# LuxLogger_V2_mcu_pwr.net
KiCad netlist of a schematic drawn in Altium Designer
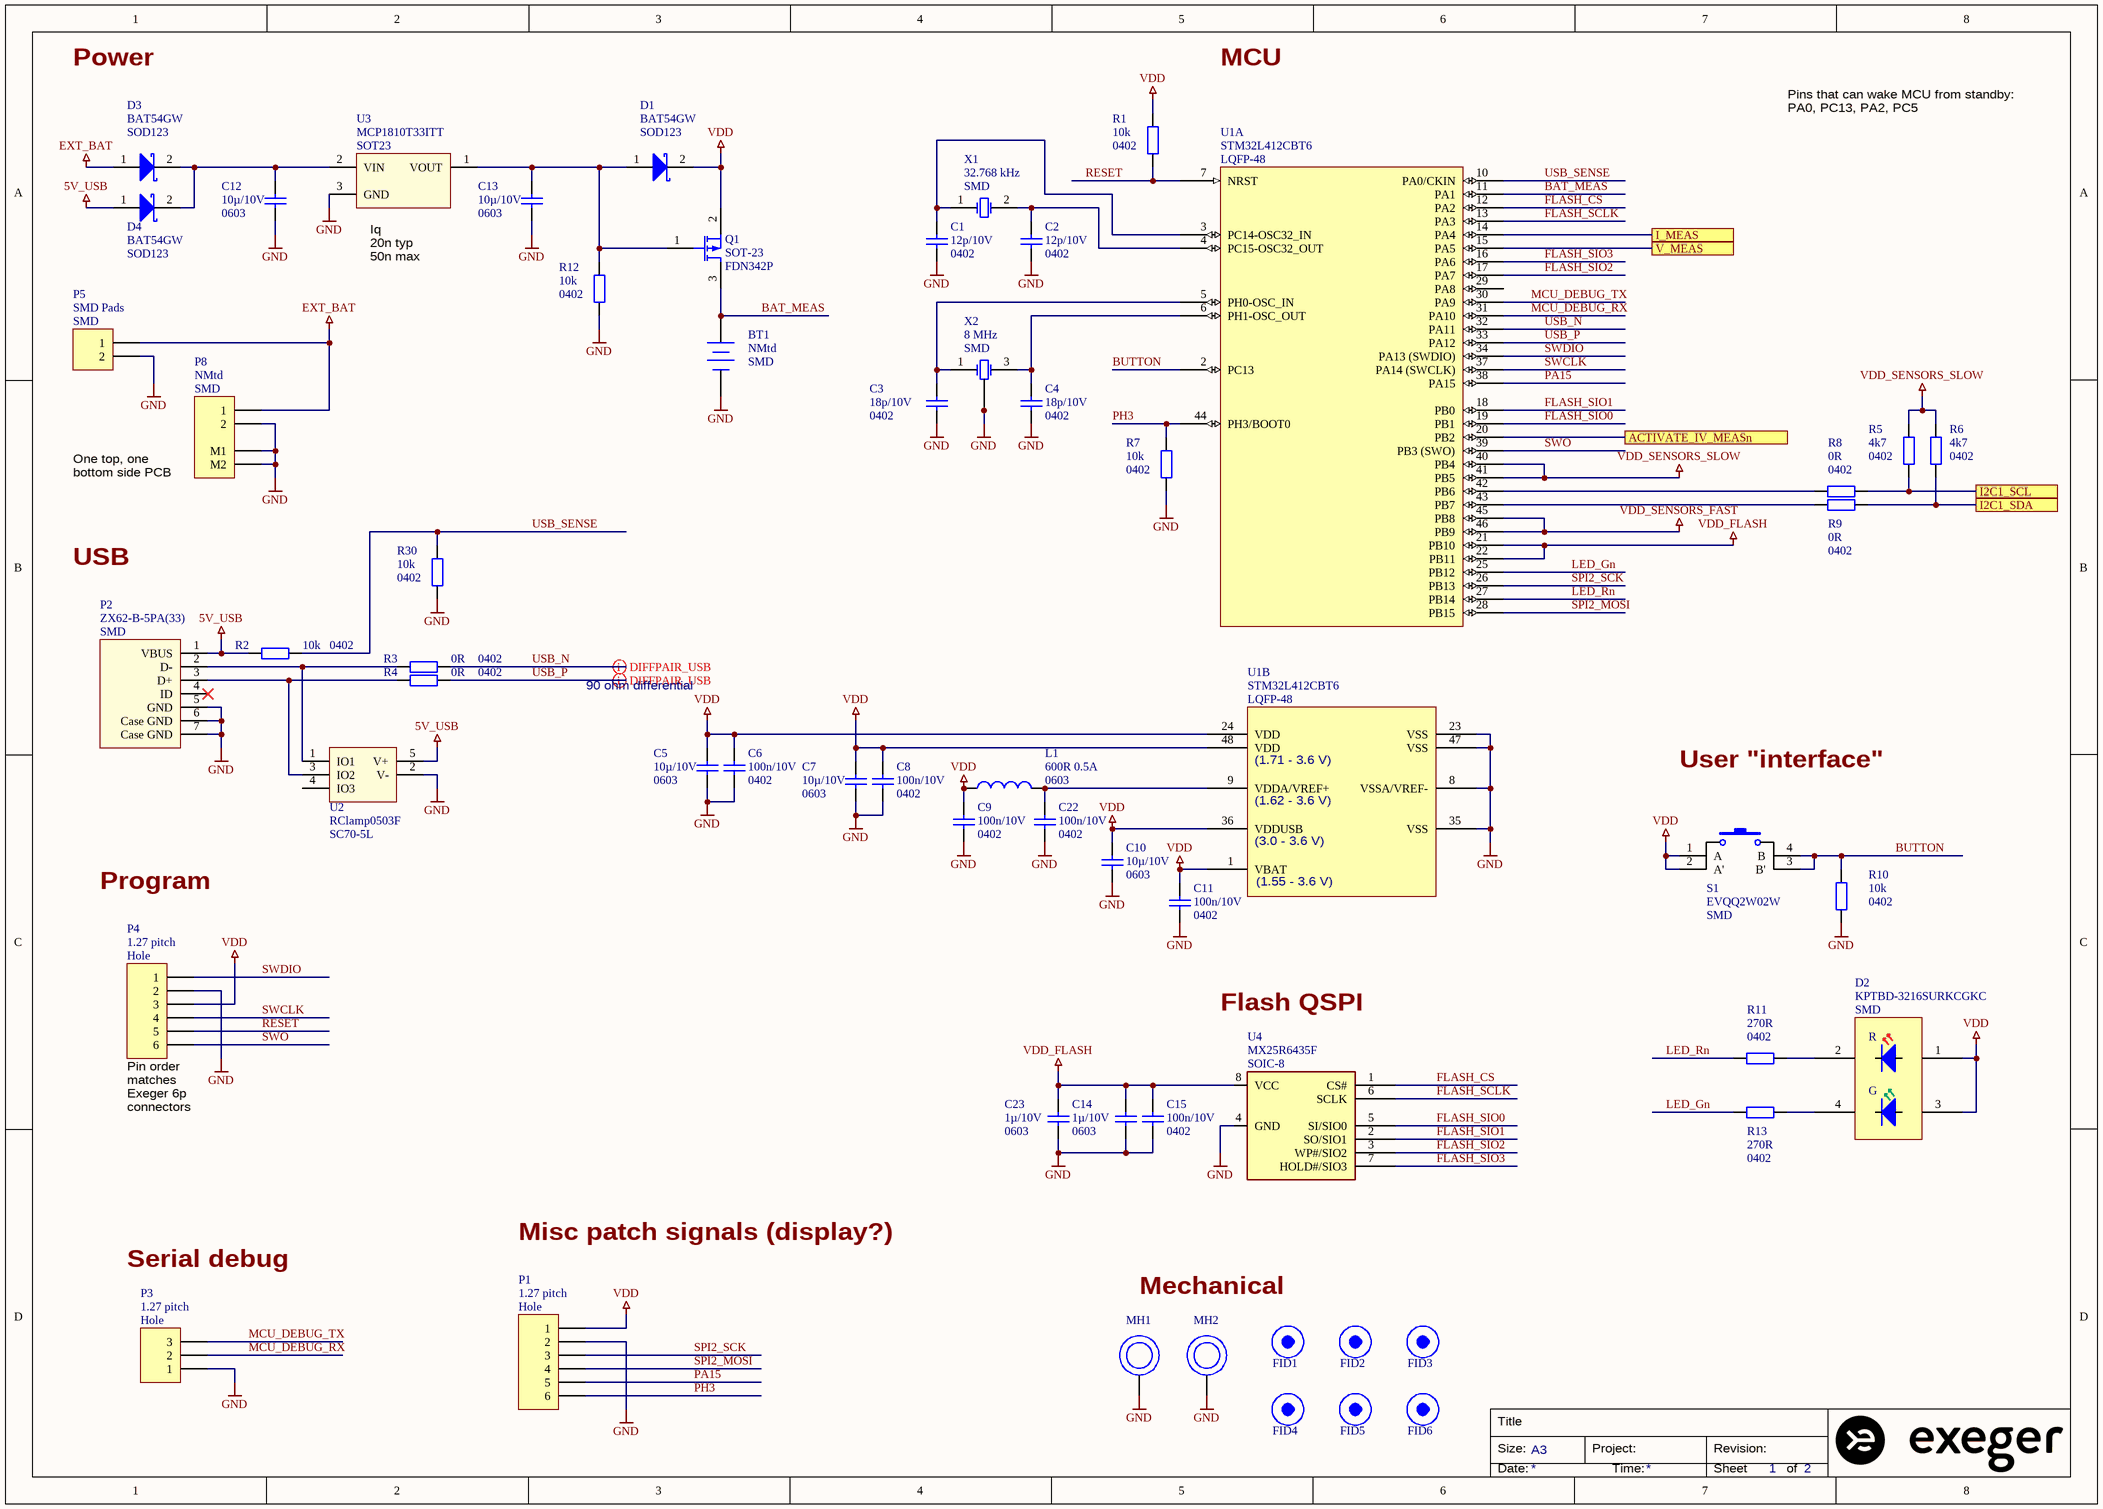
[diagram p0: LuxLogger_V2_mcu_pwr.SchDoc]

(export (version "E")
  (design (tool "Eeschema 10.0.6"))
  (components
    (comp (ref "BT1")
      (value "Alternative BU2032SM-JJ-GTR")
      (footprint "BU2032SM-HD-G")
      (description "CR2032 holder")
      (fields
        (field (name "SPECIFICATION") "NMtd")
        (field (name "PACKAGE") "SMD")
        (field (name "MANUFACTURER") "MPD")
      )
      (libsource (lib "Miscellaneous Devices") (part "Battery"))
    )
    (comp (ref "C1")
      (value "~")
      (footprint "CAP0402")
      (description "Capacitor")
      (fields (field (name "SPECIFICATION") "12p/10V") (field (name "PACKAGE") "0402"))
      (libsource (lib "Miscellaneous Devices") (part "Cap"))
    )
    (comp (ref "C2")
      (value "~")
      (footprint "CAP0402")
      (description "Capacitor")
      (fields (field (name "SPECIFICATION") "12p/10V") (field (name "PACKAGE") "0402"))
      (libsource (lib "Miscellaneous Devices") (part "Cap"))
    )
    (comp (ref "C3")
      (value "~")
      (footprint "CAP0402")
      (description "Capacitor")
      (fields (field (name "SPECIFICATION") "18p/10V") (field (name "PACKAGE") "0402"))
      (libsource (lib "Miscellaneous Devices") (part "Cap"))
    )
    (comp (ref "C4")
      (value "~")
      (footprint "CAP0402")
      (description "Capacitor")
      (fields (field (name "SPECIFICATION") "18p/10V") (field (name "PACKAGE") "0402"))
      (libsource (lib "Miscellaneous Devices") (part "Cap"))
    )
    (comp (ref "C5")
      (value "~")
      (footprint "CAP0603")
      (description "Capacitor")
      (fields (field (name "SPECIFICATION") "10µ/10V") (field (name "PACKAGE") "0603"))
      (libsource (lib "Miscellaneous Devices") (part "Cap"))
    )
    (comp (ref "C6")
      (value "~")
      (footprint "CAP0402")
      (description "Capacitor")
      (fields (field (name "SPECIFICATION") "100n/10V") (field (name "PACKAGE") "0402"))
      (libsource (lib "Miscellaneous Devices") (part "Cap"))
    )
    (comp (ref "C7")
      (value "~")
      (footprint "CAP0603")
      (description "Capacitor")
      (fields (field (name "SPECIFICATION") "10µ/10V") (field (name "PACKAGE") "0603"))
      (libsource (lib "Miscellaneous Devices") (part "Cap"))
    )
    (comp (ref "C8")
      (value "~")
      (footprint "CAP0402")
      (description "Capacitor")
      (fields (field (name "SPECIFICATION") "100n/10V") (field (name "PACKAGE") "0402"))
      (libsource (lib "Miscellaneous Devices") (part "Cap"))
    )
    (comp (ref "C9")
      (value "~")
      (footprint "CAP0402")
      (description "Capacitor")
      (fields (field (name "SPECIFICATION") "100n/10V") (field (name "PACKAGE") "0402"))
      (libsource (lib "Miscellaneous Devices") (part "Cap"))
    )
    (comp (ref "C10")
      (value "~")
      (footprint "CAP0603")
      (description "Capacitor")
      (fields (field (name "SPECIFICATION") "10µ/10V") (field (name "PACKAGE") "0603"))
      (libsource (lib "Miscellaneous Devices") (part "Cap"))
    )
    (comp (ref "C11")
      (value "~")
      (footprint "CAP0402")
      (description "Capacitor")
      (fields (field (name "SPECIFICATION") "100n/10V") (field (name "PACKAGE") "0402"))
      (libsource (lib "Miscellaneous Devices") (part "Cap"))
    )
    (comp (ref "C12")
      (value "~")
      (footprint "CAP0603")
      (description "Capacitor")
      (fields (field (name "SPECIFICATION") "10µ/10V") (field (name "PACKAGE") "0603"))
      (libsource (lib "Miscellaneous Devices") (part "Cap"))
    )
    (comp (ref "C13")
      (value "~")
      (footprint "CAP0603")
      (description "Capacitor")
      (fields (field (name "SPECIFICATION") "10µ/10V") (field (name "PACKAGE") "0603"))
      (libsource (lib "Miscellaneous Devices") (part "Cap"))
    )
    (comp (ref "C14")
      (value "~")
      (footprint "CAP0603")
      (description "Capacitor")
      (fields (field (name "SPECIFICATION") "1µ/10V") (field (name "PACKAGE") "0603"))
      (libsource (lib "Miscellaneous Devices") (part "Cap"))
    )
    (comp (ref "C15")
      (value "~")
      (footprint "CAP0402")
      (description "Capacitor")
      (fields (field (name "SPECIFICATION") "100n/10V") (field (name "PACKAGE") "0402"))
      (libsource (lib "Miscellaneous Devices") (part "Cap"))
    )
    (comp (ref "C22")
      (value "~")
      (footprint "CAP0402")
      (description "Capacitor")
      (fields (field (name "SPECIFICATION") "100n/10V") (field (name "PACKAGE") "0402"))
      (libsource (lib "Miscellaneous Devices") (part "Cap"))
    )
    (comp (ref "C23")
      (value "~")
      (footprint "CAP0603")
      (description "Capacitor")
      (fields (field (name "SPECIFICATION") "1µ/10V") (field (name "PACKAGE") "0603"))
      (libsource (lib "Miscellaneous Devices") (part "Cap"))
    )
    (comp (ref "D1")
      (value "Alternative ON BAT54T1GOSCT-ND")
      (footprint "SOD123 SODFL360X130-2N")
      (description "Schottky Diode")
      (fields
        (field (name "MANUFACTURER") "NEXPERIA")
        (field (name "PACKAGE") "SOD123")
        (field (name "SPECIFICATION") "BAT54GW")
      )
      (libsource (lib "Exeger_schematic_library") (part "D Schottky"))
    )
    (comp (ref "D2")
      (value "~")
      (footprint "KPTBD-3216SURKCGKC")
      (description "Red/green LED")
      (fields
        (field (name "MANUFACTURER") "KINGBRIGHT")
        (field (name "PACKAGE") "SMD")
        (field (name "SPECIFICATION") "KPTBD-3216SURKCGKC")
      )
      (libsource (lib "Exeger_schematic_library") (part "LED_RG"))
    )
    (comp (ref "D3")
      (value "Alternative ON BAT54T1GOSCT-ND")
      (footprint "SOD123 SODFL360X130-2N")
      (description "Schottky Diode")
      (fields
        (field (name "MANUFACTURER") "NEXPERIA")
        (field (name "PACKAGE") "SOD123")
        (field (name "SPECIFICATION") "BAT54GW")
      )
      (libsource (lib "Exeger_schematic_library") (part "D Schottky"))
    )
    (comp (ref "D4")
      (value "Alternative ON BAT54T1GOSCT-ND")
      (footprint "SOD123 SODFL360X130-2N")
      (description "Schottky Diode")
      (fields
        (field (name "MANUFACTURER") "NEXPERIA")
        (field (name "PACKAGE") "SOD123")
        (field (name "SPECIFICATION") "BAT54GW")
      )
      (libsource (lib "Exeger_schematic_library") (part "D Schottky"))
    )
    (comp (ref "FID1")
      (value "Fiducial")
      (footprint "FIDUCIAL_02_small")
      (libsource (lib "Exeger_schematic_library") (part "Fiducial"))
    )
    (comp (ref "FID2")
      (value "Fiducial")
      (footprint "FIDUCIAL_02_small")
      (libsource (lib "Exeger_schematic_library") (part "Fiducial"))
    )
    (comp (ref "FID3")
      (value "Fiducial")
      (footprint "FIDUCIAL_02_small")
      (libsource (lib "Exeger_schematic_library") (part "Fiducial"))
    )
    (comp (ref "FID4")
      (value "Fiducial")
      (footprint "FIDUCIAL_02_small")
      (libsource (lib "Exeger_schematic_library") (part "Fiducial"))
    )
    (comp (ref "FID5")
      (value "Fiducial")
      (footprint "FIDUCIAL_02_small")
      (libsource (lib "Exeger_schematic_library") (part "Fiducial"))
    )
    (comp (ref "FID6")
      (value "Fiducial")
      (footprint "FIDUCIAL_02_small")
      (libsource (lib "Exeger_schematic_library") (part "Fiducial"))
    )
    (comp (ref "L1")
      (value "~")
      (footprint "CAP0603")
      (description "Inductor")
      (fields
        (field (name "SPECIFICATION") "600R 0.5A")
        (field (name "PACKAGE") "0603")
        (field (name "MANUFACTURER") "MURATA")
      )
      (libsource (lib "Miscellaneous Devices") (part "Inductor"))
    )
    (comp (ref "MH1")
      (value "Mounting hole")
      (footprint "HOLE_PLATED_2300um")
      (libsource (lib "Exeger_schematic_library") (part "Mounting hole"))
    )
    (comp (ref "MH2")
      (value "Mounting hole")
      (footprint "HOLE_PLATED_2300um")
      (libsource (lib "Exeger_schematic_library") (part "Mounting hole"))
    )
    (comp (ref "P1")
      (value "~")
      (footprint "Header 1x6 1.27")
      (description "Header, 6-Pin")
      (fields (field (name "PACKAGE") "Hole") (field (name "SPECIFICATION") "1.27 pitch"))
      (libsource (lib "Miscellaneous Connectors") (part "Header 6"))
    )
    (comp (ref "P2")
      (value "~")
      (footprint "ZX62-B-5PA(33)")
      (description "USB Connector")
      (fields
        (field (name "MANUFACTURER") "Hirose")
        (field (name "SPECIFICATION") "ZX62-B-5PA(33)")
        (field (name "PACKAGE") "SMD")
      )
      (libsource (lib "Exeger_schematic_library") (part "ZX62-B-5PA(33)"))
    )
    (comp (ref "P3")
      (value "~")
      (footprint "Header 1x3 1.27")
      (description "Header, 3-Pin")
      (fields (field (name "PACKAGE") "Hole") (field (name "SPECIFICATION") "1.27 pitch"))
      (libsource (lib "Miscellaneous Connectors") (part "Header 3"))
    )
    (comp (ref "P4")
      (value "~")
      (footprint "Header 1x6 1.27")
      (description "Header, 6-Pin")
      (fields (field (name "PACKAGE") "Hole") (field (name "SPECIFICATION") "1.27 pitch"))
      (libsource (lib "Miscellaneous Connectors") (part "Header 6"))
    )
    (comp (ref "P5")
      (value "~")
      (footprint "2x1 blank pads_2")
      (description "Header, 2-Pin")
      (fields (field (name "PACKAGE") "SMD") (field (name "SPECIFICATION") "SMD Pads"))
      (libsource (lib "Miscellaneous Connectors") (part "Header 2"))
    )
    (comp (ref "P8")
      (value "~")
      (footprint "JST_S2B-PH-SM4-TB")
      (description "Header, 2-Pin, 2 mech pins")
      (fields
        (field (name "MANUFACTURER") "JST")
        (field (name "PACKAGE") "SMD")
        (field (name "SPECIFICATION") "NMtd")
      )
      (libsource (lib "Exeger_schematic_library") (part "Header 2+2 Mech"))
    )
    (comp (ref "Q1")
      (value "~")
      (footprint "SOT23-3")
      (description "P-Channel MOSFET")
      (fields
        (field (name "MANUFACTURER") "ON")
        (field (name "PACKAGE") "SOT-23")
        (field (name "SPECIFICATION") "FDN342P")
      )
      (libsource (lib "Exeger_schematic_library") (part "MOSFET-P"))
    )
    (comp (ref "R1")
      (value "~")
      (footprint "RES0402")
      (description "Resistor")
      (fields (field (name "PACKAGE") "0402") (field (name "SPECIFICATION") "10k"))
      (libsource (lib "") (part "Res2_1"))
    )
    (comp (ref "R2")
      (value "~")
      (footprint "RES0402")
      (description "Resistor")
      (fields (field (name "PACKAGE") "0402") (field (name "SPECIFICATION") "10k"))
      (libsource (lib "Miscellaneous Devices") (part "Res2"))
    )
    (comp (ref "R3")
      (value "~")
      (footprint "RES0402")
      (description "Resistor")
      (fields (field (name "PACKAGE") "0402") (field (name "SPECIFICATION") "0R"))
      (libsource (lib "Miscellaneous Devices") (part "Res2"))
    )
    (comp (ref "R4")
      (value "~")
      (footprint "RES0402")
      (description "Resistor")
      (fields (field (name "PACKAGE") "0402") (field (name "SPECIFICATION") "0R"))
      (libsource (lib "Miscellaneous Devices") (part "Res2"))
    )
    (comp (ref "R5")
      (value "~")
      (footprint "RES0402")
      (description "Resistor")
      (fields (field (name "PACKAGE") "0402") (field (name "SPECIFICATION") "4k7"))
      (libsource (lib "") (part "Res2_1"))
    )
    (comp (ref "R6")
      (value "~")
      (footprint "RES0402")
      (description "Resistor")
      (fields (field (name "PACKAGE") "0402") (field (name "SPECIFICATION") "4k7"))
      (libsource (lib "") (part "Res2_1"))
    )
    (comp (ref "R7")
      (value "~")
      (footprint "RES0402")
      (description "Resistor")
      (fields (field (name "PACKAGE") "0402") (field (name "SPECIFICATION") "10k"))
      (libsource (lib "") (part "Res2_1"))
    )
    (comp (ref "R8")
      (value "~")
      (footprint "RES0402")
      (description "Resistor")
      (fields (field (name "PACKAGE") "0402") (field (name "SPECIFICATION") "0R"))
      (libsource (lib "Miscellaneous Devices") (part "Res2"))
    )
    (comp (ref "R9")
      (value "~")
      (footprint "RES0402")
      (description "Resistor")
      (fields (field (name "PACKAGE") "0402") (field (name "SPECIFICATION") "0R"))
      (libsource (lib "Miscellaneous Devices") (part "Res2"))
    )
    (comp (ref "R10")
      (value "~")
      (footprint "RES0402")
      (description "Resistor")
      (fields (field (name "PACKAGE") "0402") (field (name "SPECIFICATION") "10k"))
      (libsource (lib "") (part "Res2_1"))
    )
    (comp (ref "R11")
      (value "~")
      (footprint "RES0402")
      (description "Resistor")
      (fields (field (name "PACKAGE") "0402") (field (name "SPECIFICATION") "270R"))
      (libsource (lib "Miscellaneous Devices") (part "Res2"))
    )
    (comp (ref "R12")
      (value "~")
      (footprint "RES0402")
      (description "Resistor")
      (fields (field (name "PACKAGE") "0402") (field (name "SPECIFICATION") "10k"))
      (libsource (lib "") (part "Res2_1"))
    )
    (comp (ref "R13")
      (value "~")
      (footprint "RES0402")
      (description "Resistor")
      (fields (field (name "PACKAGE") "0402") (field (name "SPECIFICATION") "270R"))
      (libsource (lib "Miscellaneous Devices") (part "Res2"))
    )
    (comp (ref "R30")
      (value "~")
      (footprint "RES0402")
      (description "Resistor")
      (fields (field (name "PACKAGE") "0402") (field (name "SPECIFICATION") "10k"))
      (libsource (lib "") (part "Res2_1"))
    )
    (comp (ref "S1")
      (value "~")
      (footprint "EVQQ2W02W")
      (description "Switch")
      (fields
        (field (name "MANUFACTURER") "PANASONIC")
        (field (name "SPECIFICATION") "EVQQ2W02W")
        (field (name "PACKAGE") "SMD")
      )
      (libsource (lib "Exeger_schematic_library") (part "SW_EVQQ2"))
    )
    (comp (ref "U1")
      (value "~")
      (footprint "TSQFP50P900X900X160-48N")
      (description "MCU")
      (fields
        (field (name "SPECIFICATION") "STM32L412CBT6")
        (field (name "PACKAGE") "LQFP-48")
        (field (name "MANUFACTURER") "ST")
      )
      (libsource (lib "Exeger_schematic_library") (part "STM32L412CB_2"))
    )
    (comp (ref "U2")
      (value "~")
      (footprint "SC-70 5L")
      (description "TVS array USB")
      (fields
        (field (name "MANUFACTURER") "SEMTECH")
        (field (name "PACKAGE") "SC70-5L")
        (field (name "SPECIFICATION") "RClamp0503F")
      )
      (libsource (lib "Exeger_schematic_library") (part "RClamp0503F"))
    )
    (comp (ref "U3")
      (value "~")
      (footprint "SOT23-3")
      (description "3V3 LDO low iq")
      (fields
        (field (name "MANUFACTURER") "MICROCHIP")
        (field (name "SPECIFICATION") "MCP1810T33ITT")
        (field (name "PACKAGE") "SOT23")
      )
      (libsource (lib "Exeger_schematic_library") (part "MCP1810TxxxTT"))
    )
    (comp (ref "U4")
      (value "~")
      (footprint "SO_8_W")
      (description "ULTRA LOW POWER, 64M-BIT FLASH MEMORY")
      (fields
        (field (name "MANUFACTURER") "Macronix")
        (field (name "PACKAGE") "SOIC-8")
        (field (name "SPECIFICATION") "MX25R6435F")
      )
      (libsource (lib "Exeger_schematic_library") (part "MX25R6435F_SO8"))
    )
    (comp (ref "X1")
      (value "~")
      (footprint "FC-135")
      (description "32.768 kHz Crystal")
      (fields
        (field (name "MANUFACTURER") "EPSON")
        (field (name "PACKAGE") "SMD")
        (field (name "SPECIFICATION") "32.768 kHz")
      )
      (libsource (lib "Exeger_schematic_library") (part "XTAL 2pin"))
    )
    (comp (ref "X2")
      (value "~")
      (footprint "ABM3B")
      (description "Crystal")
      (fields
        (field (name "MANUFACTURER") "ABRACON")
        (field (name "SPECIFICATION") "8 MHz")
        (field (name "PACKAGE") "SMD")
      )
      (libsource (lib "Exeger_schematic_library") (part "XTAL 4pin"))
    )
  )
  (nets
    (net (code "1") (name "/ACTIVATE_IV_MEASn") (class "Default")
      (node (ref "U1") (pin "20") (pinfunction "PB2_20") (pintype "bidirectional"))
    )
    (net (code "2") (name "/BAT_MEAS") (class "Default")
      (node (ref "BT1") (pin "1") (pinfunction "+_1") (pintype "passive"))
      (node (ref "Q1") (pin "3") (pinfunction "D_3") (pintype "passive"))
      (node (ref "U1") (pin "11") (pinfunction "PA1_11") (pintype "bidirectional"))
    )
    (net (code "3") (name "/BUTTON") (class "Default")
      (node (ref "R10") (pin "2") (pinfunction "2_2") (pintype "passive"))
      (node (ref "S1") (pin "3") (pinfunction "B'_3") (pintype "passive"))
      (node (ref "S1") (pin "4") (pinfunction "B_4") (pintype "passive"))
      (node (ref "U1") (pin "2") (pinfunction "PC13_2") (pintype "bidirectional"))
    )
    (net (code "4") (name "/FLASH_CS") (class "Default")
      (node (ref "U1") (pin "12") (pinfunction "PA2_12") (pintype "bidirectional"))
      (node (ref "U4") (pin "1") (pinfunction "CS#_1") (pintype "passive"))
    )
    (net (code "5") (name "/FLASH_SCLK") (class "Default")
      (node (ref "U1") (pin "13") (pinfunction "PA3_13") (pintype "bidirectional"))
      (node (ref "U4") (pin "6") (pinfunction "SCLK_6") (pintype "passive"))
    )
    (net (code "6") (name "/FLASH_SIO0") (class "Default")
      (node (ref "U1") (pin "19") (pinfunction "PB1_19") (pintype "bidirectional"))
      (node (ref "U4") (pin "5") (pinfunction "SI/SIO0_5") (pintype "passive"))
    )
    (net (code "7") (name "/FLASH_SIO1") (class "Default")
      (node (ref "U1") (pin "18") (pinfunction "PB0_18") (pintype "bidirectional"))
      (node (ref "U4") (pin "2") (pinfunction "SO/SIO1_2") (pintype "passive"))
    )
    (net (code "8") (name "/FLASH_SIO2") (class "Default")
      (node (ref "U1") (pin "17") (pinfunction "PA7_17") (pintype "bidirectional"))
      (node (ref "U4") (pin "3") (pinfunction "WP#/SIO2_3") (pintype "passive"))
    )
    (net (code "9") (name "/FLASH_SIO3") (class "Default")
      (node (ref "U1") (pin "16") (pinfunction "PA6_16") (pintype "bidirectional"))
      (node (ref "U4") (pin "7") (pinfunction "HOLD#/SIO3_7") (pintype "passive"))
    )
    (net (code "10") (name "/I2C1_SCL") (class "Default")
      (node (ref "R5") (pin "1") (pinfunction "1_1") (pintype "passive"))
      (node (ref "R8") (pin "1") (pinfunction "1_1") (pintype "passive"))
    )
    (net (code "11") (name "/I2C1_SDA") (class "Default")
      (node (ref "R6") (pin "1") (pinfunction "1_1") (pintype "passive"))
      (node (ref "R9") (pin "1") (pinfunction "1_1") (pintype "passive"))
    )
    (net (code "12") (name "/I_MEAS") (class "Default")
      (node (ref "U1") (pin "14") (pinfunction "PA4_14") (pintype "bidirectional"))
    )
    (net (code "13") (name "/LED_Gn") (class "Default")
      (node (ref "R13") (pin "2") (pinfunction "2_2") (pintype "passive"))
      (node (ref "U1") (pin "25") (pinfunction "PB12_25") (pintype "bidirectional"))
    )
    (net (code "14") (name "/LED_Rn") (class "Default")
      (node (ref "R11") (pin "2") (pinfunction "2_2") (pintype "passive"))
      (node (ref "U1") (pin "27") (pinfunction "PB14_27") (pintype "bidirectional"))
    )
    (net (code "15") (name "/MCU_DEBUG_RX") (class "Default")
      (node (ref "P3") (pin "2") (pinfunction "2_2") (pintype "passive"))
      (node (ref "U1") (pin "31") (pinfunction "PA10_31") (pintype "bidirectional"))
    )
    (net (code "16") (name "/MCU_DEBUG_TX") (class "Default")
      (node (ref "P3") (pin "3") (pinfunction "3_3") (pintype "passive"))
      (node (ref "U1") (pin "30") (pinfunction "PA9_30") (pintype "bidirectional"))
    )
    (net (code "17") (name "/PA15") (class "Default")
      (node (ref "P1") (pin "5") (pinfunction "5_5") (pintype "passive"))
      (node (ref "U1") (pin "38") (pinfunction "PA15_38") (pintype "bidirectional"))
    )
    (net (code "18") (name "/PH3") (class "Default")
      (node (ref "P1") (pin "6") (pinfunction "6_6") (pintype "passive"))
      (node (ref "R7") (pin "2") (pinfunction "2_2") (pintype "passive"))
      (node (ref "U1") (pin "44") (pinfunction "PH3/BOOT0_44") (pintype "bidirectional"))
    )
    (net (code "19") (name "/RESET") (class "Default")
      (node (ref "P4") (pin "5") (pinfunction "5_5") (pintype "passive"))
      (node (ref "R1") (pin "1") (pinfunction "1_1") (pintype "passive"))
      (node (ref "U1") (pin "7") (pinfunction "NRST_7") (pintype "input"))
    )
    (net (code "20") (name "/SPI2_MOSI") (class "Default")
      (node (ref "P1") (pin "4") (pinfunction "4_4") (pintype "passive"))
      (node (ref "U1") (pin "28") (pinfunction "PB15_28") (pintype "bidirectional"))
    )
    (net (code "21") (name "/SPI2_SCK") (class "Default")
      (node (ref "P1") (pin "3") (pinfunction "3_3") (pintype "passive"))
      (node (ref "U1") (pin "26") (pinfunction "PB13_26") (pintype "bidirectional"))
    )
    (net (code "22") (name "/SWCLK") (class "Default")
      (node (ref "P4") (pin "4") (pinfunction "4_4") (pintype "passive"))
      (node (ref "U1") (pin "37") (pinfunction "PA14_(SWCLK)_37") (pintype "bidirectional"))
    )
    (net (code "23") (name "/SWDIO") (class "Default")
      (node (ref "P4") (pin "1") (pinfunction "1_1") (pintype "passive"))
      (node (ref "U1") (pin "34") (pinfunction "PA13_(SWDIO)_34") (pintype "bidirectional"))
    )
    (net (code "24") (name "/SWO") (class "Default")
      (node (ref "P4") (pin "6") (pinfunction "6_6") (pintype "passive"))
      (node (ref "U1") (pin "39") (pinfunction "PB3_(SWO)_39") (pintype "bidirectional"))
    )
    (net (code "25") (name "/USB_N") (class "Default")
      (node (ref "R3") (pin "1") (pinfunction "1_1") (pintype "passive"))
      (node (ref "U1") (pin "32") (pinfunction "PA11_32") (pintype "bidirectional"))
    )
    (net (code "26") (name "/USB_P") (class "Default")
      (node (ref "R4") (pin "1") (pinfunction "1_1") (pintype "passive"))
      (node (ref "U1") (pin "33") (pinfunction "PA12_33") (pintype "bidirectional"))
    )
    (net (code "27") (name "/USB_SENSE") (class "Default")
      (node (ref "R2") (pin "1") (pinfunction "1_1") (pintype "passive"))
      (node (ref "R30") (pin "2") (pinfunction "2_2") (pintype "passive"))
      (node (ref "U1") (pin "10") (pinfunction "PA0/CKIN_10") (pintype "bidirectional"))
    )
    (net (code "28") (name "/V_MEAS") (class "Default")
      (node (ref "U1") (pin "15") (pinfunction "PA5_15") (pintype "bidirectional"))
    )
    (net (code "29") (name "5V_USB") (class "Default")
      (node (ref "D4") (pin "1") (pinfunction "A_1") (pintype "passive"))
      (node (ref "P2") (pin "1") (pinfunction "VBUS_1") (pintype "power_in"))
      (node (ref "R2") (pin "2") (pinfunction "2_2") (pintype "passive"))
      (node (ref "U2") (pin "5") (pinfunction "V+_5") (pintype "power_in"))
    )
    (net (code "30") (name "EXT_BAT") (class "Default")
      (node (ref "D3") (pin "1") (pinfunction "A_1") (pintype "passive"))
      (node (ref "P5") (pin "1") (pinfunction "1_1") (pintype "passive"))
      (node (ref "P8") (pin "1") (pinfunction "1_1") (pintype "passive"))
    )
    (net (code "31") (name "GND") (class "Default")
      (node (ref "BT1") (pin "2") (pinfunction "-_2") (pintype "passive"))
      (node (ref "C1") (pin "1") (pinfunction "1_1") (pintype "passive"))
      (node (ref "C10") (pin "1") (pinfunction "1_1") (pintype "passive"))
      (node (ref "C11") (pin "1") (pinfunction "1_1") (pintype "passive"))
      (node (ref "C12") (pin "1") (pinfunction "1_1") (pintype "passive"))
      (node (ref "C13") (pin "1") (pinfunction "1_1") (pintype "passive"))
      (node (ref "C14") (pin "1") (pinfunction "1_1") (pintype "passive"))
      (node (ref "C15") (pin "1") (pinfunction "1_1") (pintype "passive"))
      (node (ref "C2") (pin "1") (pinfunction "1_1") (pintype "passive"))
      (node (ref "C22") (pin "1") (pinfunction "1_1") (pintype "passive"))
      (node (ref "C23") (pin "1") (pinfunction "1_1") (pintype "passive"))
      (node (ref "C3") (pin "1") (pinfunction "1_1") (pintype "passive"))
      (node (ref "C4") (pin "1") (pinfunction "1_1") (pintype "passive"))
      (node (ref "C5") (pin "1") (pinfunction "1_1") (pintype "passive"))
      (node (ref "C6") (pin "1") (pinfunction "1_1") (pintype "passive"))
      (node (ref "C7") (pin "1") (pinfunction "1_1") (pintype "passive"))
      (node (ref "C8") (pin "1") (pinfunction "1_1") (pintype "passive"))
      (node (ref "C9") (pin "1") (pinfunction "1_1") (pintype "passive"))
      (node (ref "MH1") (pin "1") (pinfunction "1_1") (pintype "passive"))
      (node (ref "MH2") (pin "1") (pinfunction "1_1") (pintype "passive"))
      (node (ref "P1") (pin "2") (pinfunction "2_2") (pintype "passive"))
      (node (ref "P2") (pin "5") (pinfunction "GND_5") (pintype "power_in"))
      (node (ref "P2") (pin "6") (pinfunction "Case_GND_6") (pintype "power_in"))
      (node (ref "P2") (pin "7") (pinfunction "Case_GND_7") (pintype "passive"))
      (node (ref "P3") (pin "1") (pinfunction "1_1") (pintype "passive"))
      (node (ref "P4") (pin "2") (pinfunction "2_2") (pintype "passive"))
      (node (ref "P5") (pin "2") (pinfunction "2_2") (pintype "passive"))
      (node (ref "P8") (pin "2") (pinfunction "2_2") (pintype "passive"))
      (node (ref "P8") (pin "3") (pinfunction "M1_3") (pintype "passive"))
      (node (ref "P8") (pin "4") (pinfunction "M2_4") (pintype "passive"))
      (node (ref "R10") (pin "1") (pinfunction "1_1") (pintype "passive"))
      (node (ref "R12") (pin "1") (pinfunction "1_1") (pintype "passive"))
      (node (ref "R30") (pin "1") (pinfunction "1_1") (pintype "passive"))
      (node (ref "R7") (pin "1") (pinfunction "1_1") (pintype "passive"))
      (node (ref "U1") (pin "23") (pinfunction "VSS_23") (pintype "power_in"))
      (node (ref "U1") (pin "35") (pinfunction "VSS_35") (pintype "power_in"))
      (node (ref "U1") (pin "47") (pinfunction "VSS_47") (pintype "power_in"))
      (node (ref "U1") (pin "8") (pinfunction "VSSA/VREF-_8") (pintype "power_in"))
      (node (ref "U2") (pin "2") (pinfunction "V-_2") (pintype "power_in"))
      (node (ref "U3") (pin "3") (pinfunction "GND_3") (pintype "power_in"))
      (node (ref "U4") (pin "4") (pinfunction "GND_4") (pintype "passive"))
      (node (ref "X2") (pin "2") (pinfunction "GND_2") (pintype "passive"))
      (node (ref "X2") (pin "4") (pinfunction "GND_4") (pintype "passive"))
    )
    (net (code "32") (name "Net-(D1-A)") (class "Default")
      (node (ref "C13") (pin "2") (pinfunction "2_2") (pintype "passive"))
      (node (ref "D1") (pin "1") (pinfunction "A_1") (pintype "passive"))
      (node (ref "Q1") (pin "1") (pinfunction "G_1") (pintype "passive"))
      (node (ref "R12") (pin "2") (pinfunction "2_2") (pintype "passive"))
      (node (ref "U3") (pin "1") (pinfunction "VOUT_1") (pintype "power_in"))
    )
    (net (code "33") (name "Net-(D2-G_K)") (class "Default")
      (node (ref "D2") (pin "4") (pinfunction "G_K_4") (pintype "passive"))
      (node (ref "R13") (pin "1") (pinfunction "1_1") (pintype "passive"))
    )
    (net (code "34") (name "Net-(D2-R_K)") (class "Default")
      (node (ref "D2") (pin "2") (pinfunction "R_K_2") (pintype "passive"))
      (node (ref "R11") (pin "1") (pinfunction "1_1") (pintype "passive"))
    )
    (net (code "35") (name "Net-(D3-K)") (class "Default")
      (node (ref "C12") (pin "2") (pinfunction "2_2") (pintype "passive"))
      (node (ref "D3") (pin "2") (pinfunction "K_2") (pintype "passive"))
      (node (ref "D4") (pin "2") (pinfunction "K_2") (pintype "passive"))
      (node (ref "U3") (pin "2") (pinfunction "VIN_2") (pintype "passive"))
    )
    (net (code "36") (name "Net-(P2-D+)") (class "Default")
      (node (ref "P2") (pin "3") (pinfunction "D+_3") (pintype "passive"))
      (node (ref "R4") (pin "2") (pinfunction "2_2") (pintype "passive"))
      (node (ref "U2") (pin "3") (pinfunction "IO2_3") (pintype "power_in"))
    )
    (net (code "37") (name "Net-(P2-D-)") (class "Default")
      (node (ref "P2") (pin "2") (pinfunction "D-_2") (pintype "passive"))
      (node (ref "R3") (pin "2") (pinfunction "2_2") (pintype "passive"))
      (node (ref "U2") (pin "1") (pinfunction "IO1_1") (pintype "power_in"))
    )
    (net (code "38") (name "Net-(U1A-PB6)") (class "Default")
      (node (ref "R8") (pin "2") (pinfunction "2_2") (pintype "passive"))
      (node (ref "U1") (pin "42") (pinfunction "PB6_42") (pintype "bidirectional"))
    )
    (net (code "39") (name "Net-(U1A-PB7)") (class "Default")
      (node (ref "R9") (pin "2") (pinfunction "2_2") (pintype "passive"))
      (node (ref "U1") (pin "43") (pinfunction "PB7_43") (pintype "bidirectional"))
    )
    (net (code "40") (name "Net-(U1A-PC14-OSC32_IN)") (class "Default")
      (node (ref "C1") (pin "2") (pinfunction "2_2") (pintype "passive"))
      (node (ref "U1") (pin "3") (pinfunction "PC14-OSC32_IN_3") (pintype "bidirectional"))
      (node (ref "X1") (pin "1") (pinfunction "OSC1_1") (pintype "passive"))
    )
    (net (code "41") (name "Net-(U1A-PC15-OSC32_OUT)") (class "Default")
      (node (ref "C2") (pin "2") (pinfunction "2_2") (pintype "passive"))
      (node (ref "U1") (pin "4") (pinfunction "PC15-OSC32_OUT_4") (pintype "bidirectional"))
      (node (ref "X1") (pin "2") (pinfunction "OSC2_2") (pintype "passive"))
    )
    (net (code "42") (name "Net-(U1A-PH0-OSC_IN)") (class "Default")
      (node (ref "C3") (pin "2") (pinfunction "2_2") (pintype "passive"))
      (node (ref "U1") (pin "5") (pinfunction "PH0-OSC_IN_5") (pintype "bidirectional"))
      (node (ref "X2") (pin "1") (pinfunction "OSC1_1") (pintype "passive"))
    )
    (net (code "43") (name "Net-(U1A-PH1-OSC_OUT)") (class "Default")
      (node (ref "C4") (pin "2") (pinfunction "2_2") (pintype "passive"))
      (node (ref "U1") (pin "6") (pinfunction "PH1-OSC_OUT_6") (pintype "bidirectional"))
      (node (ref "X2") (pin "3") (pinfunction "OSC2_3") (pintype "passive"))
    )
    (net (code "44") (name "Net-(U1B-VDDA{slash}VREF+)") (class "Default")
      (node (ref "C22") (pin "2") (pinfunction "2_2") (pintype "passive"))
      (node (ref "L1") (pin "2") (pinfunction "2_2") (pintype "passive"))
      (node (ref "U1") (pin "9") (pinfunction "VDDA/VREF+_9") (pintype "power_in"))
    )
    (net (code "45") (name "VDD") (class "Default")
      (node (ref "C10") (pin "2") (pinfunction "2_2") (pintype "passive"))
      (node (ref "C11") (pin "2") (pinfunction "2_2") (pintype "passive"))
      (node (ref "C5") (pin "2") (pinfunction "2_2") (pintype "passive"))
      (node (ref "C6") (pin "2") (pinfunction "2_2") (pintype "passive"))
      (node (ref "C7") (pin "2") (pinfunction "2_2") (pintype "passive"))
      (node (ref "C8") (pin "2") (pinfunction "2_2") (pintype "passive"))
      (node (ref "C9") (pin "2") (pinfunction "2_2") (pintype "passive"))
      (node (ref "D1") (pin "2") (pinfunction "K_2") (pintype "passive"))
      (node (ref "D2") (pin "1") (pinfunction "R_A_1") (pintype "passive"))
      (node (ref "D2") (pin "3") (pinfunction "G_A_3") (pintype "passive"))
      (node (ref "L1") (pin "1") (pinfunction "1_1") (pintype "passive"))
      (node (ref "P1") (pin "1") (pinfunction "1_1") (pintype "passive"))
      (node (ref "P4") (pin "3") (pinfunction "3_3") (pintype "passive"))
      (node (ref "Q1") (pin "2") (pinfunction "S_2") (pintype "passive"))
      (node (ref "R1") (pin "2") (pinfunction "2_2") (pintype "passive"))
      (node (ref "S1") (pin "1") (pinfunction "A_1") (pintype "passive"))
      (node (ref "S1") (pin "2") (pinfunction "A'_2") (pintype "passive"))
      (node (ref "U1") (pin "1") (pinfunction "VBAT_1") (pintype "power_in"))
      (node (ref "U1") (pin "24") (pinfunction "VDD_24") (pintype "power_in"))
      (node (ref "U1") (pin "36") (pinfunction "VDDUSB_36") (pintype "power_in"))
      (node (ref "U1") (pin "48") (pinfunction "VDD_48") (pintype "power_in"))
    )
    (net (code "46") (name "VDD_FLASH") (class "Default")
      (node (ref "C14") (pin "2") (pinfunction "2_2") (pintype "passive"))
      (node (ref "C15") (pin "2") (pinfunction "2_2") (pintype "passive"))
      (node (ref "C23") (pin "2") (pinfunction "2_2") (pintype "passive"))
      (node (ref "U1") (pin "21") (pinfunction "PB10_21") (pintype "bidirectional"))
      (node (ref "U1") (pin "22") (pinfunction "PB11_22") (pintype "bidirectional"))
      (node (ref "U4") (pin "8") (pinfunction "VCC_8") (pintype "passive"))
    )
    (net (code "47") (name "VDD_SENSORS_FAST") (class "Default")
      (node (ref "U1") (pin "45") (pinfunction "PB8_45") (pintype "bidirectional"))
      (node (ref "U1") (pin "46") (pinfunction "PB9_46") (pintype "bidirectional"))
    )
    (net (code "48") (name "VDD_SENSORS_SLOW") (class "Default")
      (node (ref "R5") (pin "2") (pinfunction "2_2") (pintype "passive"))
      (node (ref "R6") (pin "2") (pinfunction "2_2") (pintype "passive"))
      (node (ref "U1") (pin "40") (pinfunction "PB4_40") (pintype "bidirectional"))
      (node (ref "U1") (pin "41") (pinfunction "PB5_41") (pintype "bidirectional"))
    )
    (net (code "49") (name "unconnected-(P2-ID-Pad4)") (class "Default")
      (node (ref "P2") (pin "4") (pinfunction "ID_4") (pintype "passive+no_connect"))
    )
    (net (code "50") (name "unconnected-(U1A-PA8-Pad29)") (class "Default")
      (node (ref "U1") (pin "29") (pinfunction "PA8_29") (pintype "bidirectional"))
    )
    (net (code "51") (name "unconnected-(U2-IO3-Pad4)") (class "Default")
      (node (ref "U2") (pin "4") (pinfunction "IO3_4") (pintype "power_in"))
    )
  )
)
